# untitled.net
KiCad netlist of a schematic drawn in EAGLE
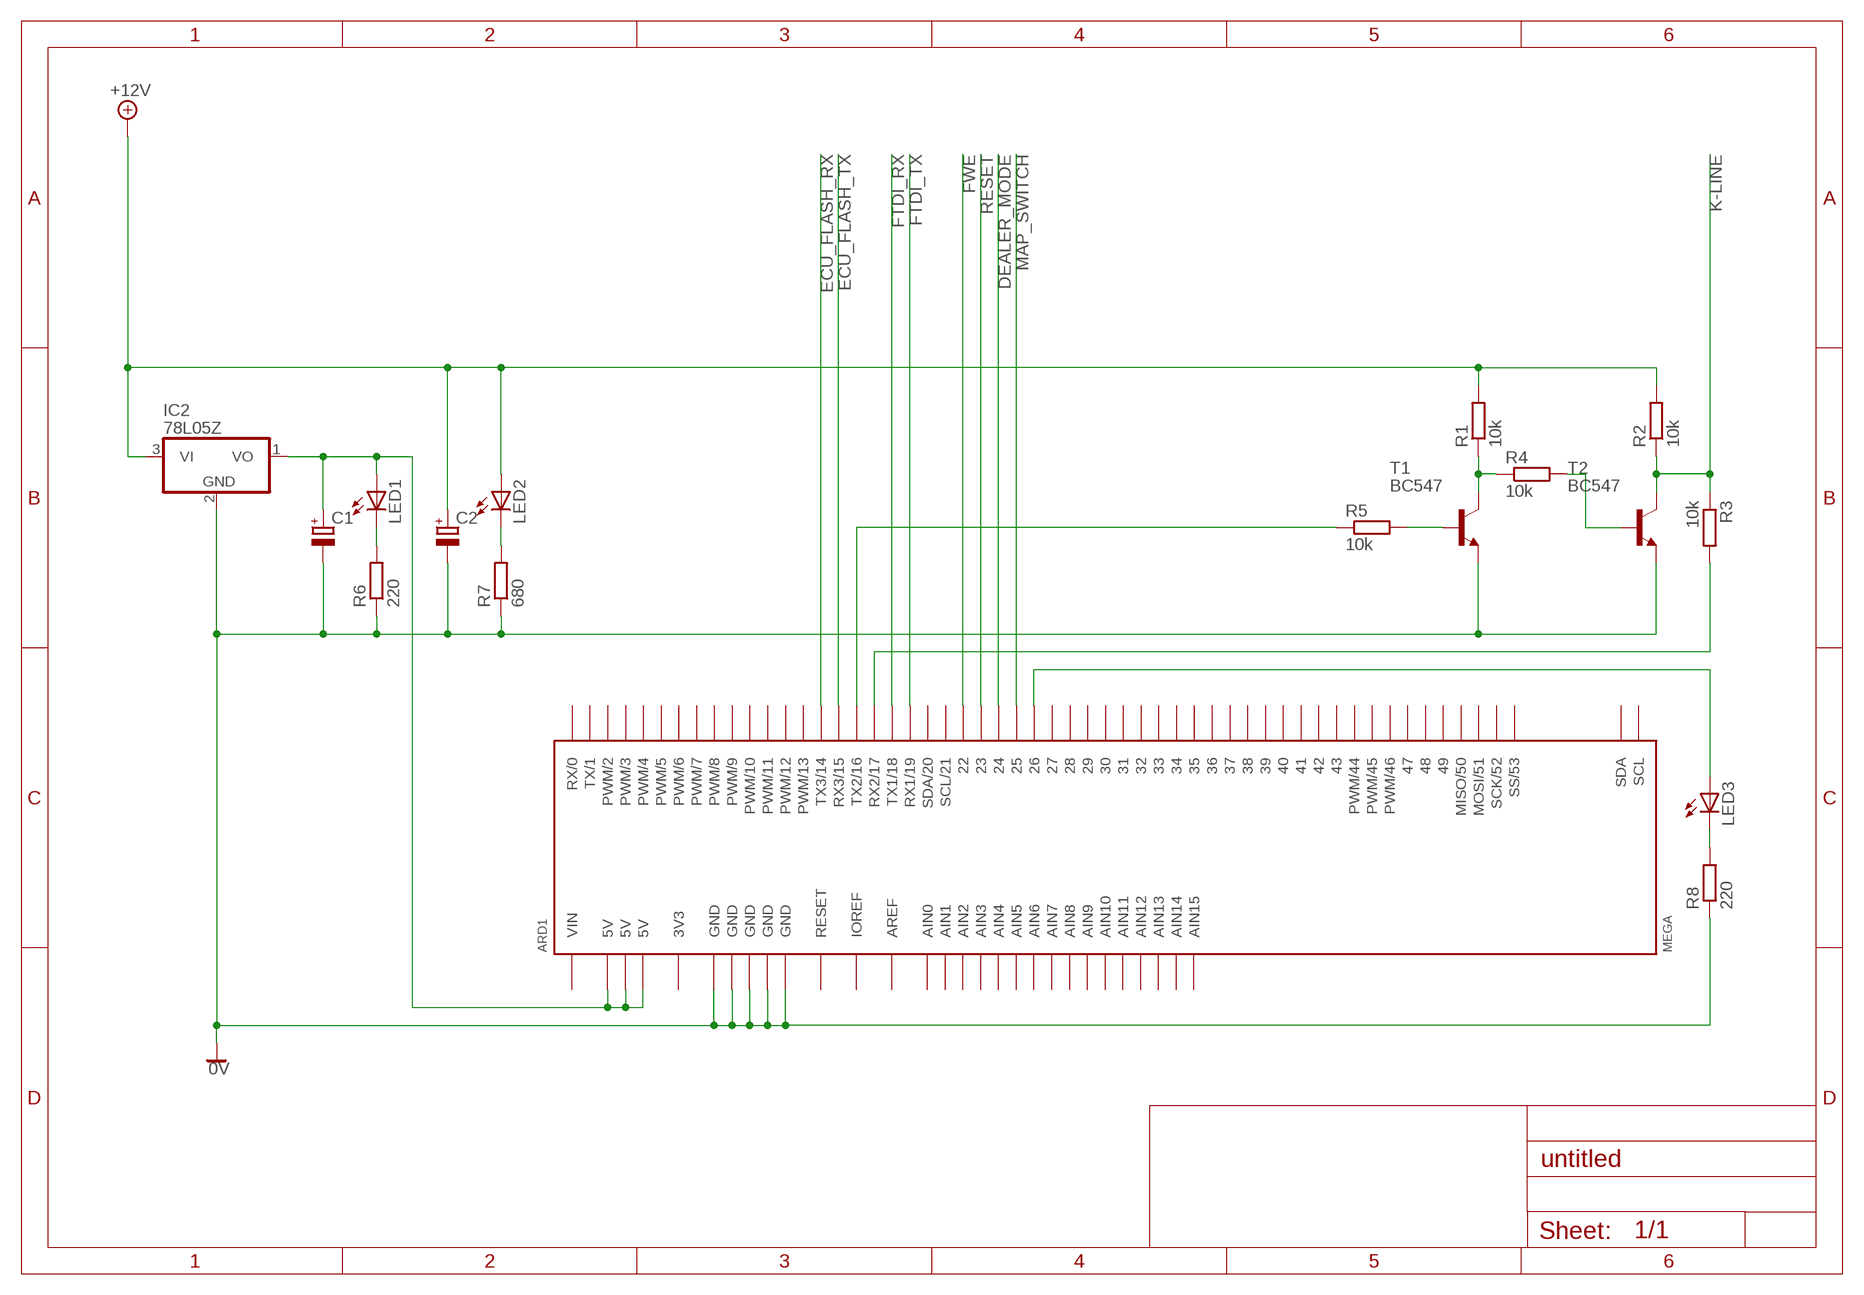
[diagram p0: schematic, sheet 1]

(export (version "E")
  (design (tool "Eeschema 10.0.6"))
  (components
    (comp (ref "ARD1")
      (value "MEGA")
      (footprint "eagle-import:MEGA")
      (libsource (lib "eagle-import") (part "MEGA"))
    )
    (comp (ref "C1")
      (value "CPOL-EUE1.8-4")
      (footprint "eagle-import:E1,8-4")
      (libsource (lib "eagle-import") (part "CPOL-EUE1.8-4"))
    )
    (comp (ref "C2")
      (value "CPOL-EUE1.8-4")
      (footprint "eagle-import:E1,8-4")
      (libsource (lib "eagle-import") (part "CPOL-EUE1.8-4"))
    )
    (comp (ref "IC2")
      (value "78L05Z")
      (footprint "eagle-import:TO92")
      (libsource (lib "eagle-import") (part "78ZL05"))
    )
    (comp (ref "LED1")
      (value "LED")
      (footprint "eagle-import:SMARTLED-TTW")
      (libsource (lib "eagle-import") (part "LED"))
    )
    (comp (ref "LED2")
      (value "LED")
      (footprint "eagle-import:SMARTLED-TTW")
      (libsource (lib "eagle-import") (part "LED"))
    )
    (comp (ref "LED3")
      (value "LED")
      (footprint "eagle-import:SMARTLED-TTW")
      (libsource (lib "eagle-import") (part "LED"))
    )
    (comp (ref "R1")
      (value "10k")
      (footprint "eagle-import:0204_5")
      (libsource (lib "eagle-import") (part "R-EU_0204/5"))
    )
    (comp (ref "R2")
      (value "10k")
      (footprint "eagle-import:0204_5")
      (libsource (lib "eagle-import") (part "R-EU_0204/5"))
    )
    (comp (ref "R3")
      (value "10k")
      (footprint "eagle-import:0204_5")
      (libsource (lib "eagle-import") (part "R-EU_0204/5"))
    )
    (comp (ref "R4")
      (value "10k")
      (footprint "eagle-import:0204_5")
      (libsource (lib "eagle-import") (part "R-EU_0204/5"))
    )
    (comp (ref "R5")
      (value "10k")
      (footprint "eagle-import:0204_5")
      (libsource (lib "eagle-import") (part "R-EU_0204/5"))
    )
    (comp (ref "R6")
      (value "220")
      (footprint "eagle-import:0204_5")
      (libsource (lib "eagle-import") (part "R-EU_0204/5"))
    )
    (comp (ref "R7")
      (value "680")
      (footprint "eagle-import:0204_5")
      (libsource (lib "eagle-import") (part "R-EU_0204/5"))
    )
    (comp (ref "R8")
      (value "220")
      (footprint "eagle-import:0204_5")
      (libsource (lib "eagle-import") (part "R-EU_0204/5"))
    )
    (comp (ref "T1")
      (value "BC547")
      (footprint "eagle-import:TO92")
      (libsource (lib "eagle-import") (part "BC547"))
    )
    (comp (ref "T2")
      (value "BC547")
      (footprint "eagle-import:TO92")
      (libsource (lib "eagle-import") (part "BC547"))
    )
  )
  (nets
    (net (code "1") (name "+12V") (class "Default")
      (node (ref "C2") (pin "+") (pinfunction "+_+") (pintype "passive"))
      (node (ref "IC2") (pin "3") (pinfunction "VI_3") (pintype "input"))
      (node (ref "LED2") (pin "A@1") (pinfunction "A_A@1") (pintype "passive"))
      (node (ref "R1") (pin "2") (pinfunction "2_2") (pintype "passive"))
      (node (ref "R2") (pin "2") (pinfunction "2_2") (pintype "passive"))
    )
    (net (code "2") (name "/3V3") (class "Default")
      (node (ref "ARD1") (pin "3V3") (pinfunction "3V3_3V3") (pintype "power_in"))
    )
    (net (code "3") (name "/AREF") (class "Default")
      (node (ref "ARD1") (pin "AREF") (pinfunction "AREF_AREF") (pintype "power_in"))
    )
    (net (code "4") (name "/DEALER_MODE") (class "Default")
      (node (ref "ARD1") (pin "24") (pinfunction "24_24") (pintype "bidirectional"))
    )
    (net (code "5") (name "/ECU_FLASH_RX") (class "Default")
      (node (ref "ARD1") (pin "14") (pinfunction "TX3/14_14") (pintype "bidirectional"))
    )
    (net (code "6") (name "/ECU_FLASH_TX") (class "Default")
      (node (ref "ARD1") (pin "15") (pinfunction "RX3/15_15") (pintype "bidirectional"))
    )
    (net (code "7") (name "/FTDI_RX") (class "Default")
      (node (ref "ARD1") (pin "18") (pinfunction "TX1/18_18") (pintype "bidirectional"))
    )
    (net (code "8") (name "/FTDI_TX") (class "Default")
      (node (ref "ARD1") (pin "19") (pinfunction "RX1/19_19") (pintype "bidirectional"))
    )
    (net (code "9") (name "/FWE") (class "Default")
      (node (ref "ARD1") (pin "22") (pinfunction "22_22") (pintype "bidirectional"))
    )
    (net (code "10") (name "/IOREF") (class "Default")
      (node (ref "ARD1") (pin "IOREF") (pinfunction "IOREF_IOREF") (pintype "power_in"))
    )
    (net (code "11") (name "/K-LINE") (class "Default")
      (node (ref "R2") (pin "1") (pinfunction "1_1") (pintype "passive"))
      (node (ref "R3") (pin "1") (pinfunction "1_1") (pintype "passive"))
      (node (ref "T2") (pin "3") (pinfunction "C_3") (pintype "passive"))
    )
    (net (code "12") (name "/MAP_SWITCH") (class "Default")
      (node (ref "ARD1") (pin "25") (pinfunction "25_25") (pintype "bidirectional"))
    )
    (net (code "13") (name "/RESET") (class "Default")
      (node (ref "ARD1") (pin "23") (pinfunction "23_23") (pintype "bidirectional"))
    )
    (net (code "14") (name "/VIN") (class "Default")
      (node (ref "ARD1") (pin "VIN") (pinfunction "VIN_VIN") (pintype "power_in"))
    )
    (net (code "15") (name "0V") (class "Default")
      (node (ref "ARD1") (pin "GND1") (pinfunction "GND_GND1") (pintype "power_in"))
      (node (ref "ARD1") (pin "GND2") (pinfunction "GND_GND2") (pintype "power_in"))
      (node (ref "ARD1") (pin "GND3") (pinfunction "GND_GND3") (pintype "power_in"))
      (node (ref "ARD1") (pin "GND4") (pinfunction "GND_GND4") (pintype "power_in"))
      (node (ref "ARD1") (pin "GND5") (pinfunction "GND_GND5") (pintype "power_in"))
      (node (ref "C1") (pin "-") (pinfunction "-_-") (pintype "passive"))
      (node (ref "C2") (pin "-") (pinfunction "-_-") (pintype "passive"))
      (node (ref "IC2") (pin "2") (pinfunction "GND_2") (pintype "passive"))
      (node (ref "R6") (pin "1") (pinfunction "1_1") (pintype "passive"))
      (node (ref "R7") (pin "1") (pinfunction "1_1") (pintype "passive"))
      (node (ref "R8") (pin "1") (pinfunction "1_1") (pintype "passive"))
      (node (ref "T1") (pin "1") (pinfunction "E_1") (pintype "passive"))
      (node (ref "T2") (pin "1") (pinfunction "E_1") (pintype "passive"))
    )
    (net (code "16") (name "Net-(ARD1-RX2{slash}17)") (class "Default")
      (node (ref "ARD1") (pin "17") (pinfunction "RX2/17_17") (pintype "bidirectional"))
      (node (ref "R3") (pin "2") (pinfunction "2_2") (pintype "passive"))
    )
    (net (code "17") (name "Net-(ARD1-TX2{slash}16)") (class "Default")
      (node (ref "ARD1") (pin "16") (pinfunction "TX2/16_16") (pintype "bidirectional"))
      (node (ref "R5") (pin "1") (pinfunction "1_1") (pintype "passive"))
    )
    (net (code "18") (name "Net-(IC2-VO)") (class "Default")
      (node (ref "ARD1") (pin "5V1") (pinfunction "5V_5V1") (pintype "power_in"))
      (node (ref "ARD1") (pin "5V2") (pinfunction "5V_5V2") (pintype "power_in"))
      (node (ref "ARD1") (pin "5V3") (pinfunction "5V_5V3") (pintype "power_in"))
      (node (ref "C1") (pin "+") (pinfunction "+_+") (pintype "passive"))
      (node (ref "IC2") (pin "1") (pinfunction "VO_1") (pintype "passive"))
      (node (ref "LED1") (pin "A@1") (pinfunction "A_A@1") (pintype "passive"))
    )
    (net (code "19") (name "Net-(LED1-C)") (class "Default")
      (node (ref "LED1") (pin "C@1") (pinfunction "C_C@1") (pintype "passive"))
      (node (ref "R6") (pin "2") (pinfunction "2_2") (pintype "passive"))
    )
    (net (code "20") (name "Net-(LED2-C)") (class "Default")
      (node (ref "LED2") (pin "C@1") (pinfunction "C_C@1") (pintype "passive"))
      (node (ref "R7") (pin "2") (pinfunction "2_2") (pintype "passive"))
    )
    (net (code "21") (name "Net-(LED3-A)") (class "Default")
      (node (ref "ARD1") (pin "26") (pinfunction "26_26") (pintype "bidirectional"))
      (node (ref "LED3") (pin "A@1") (pinfunction "A_A@1") (pintype "passive"))
    )
    (net (code "22") (name "Net-(LED3-C)") (class "Default")
      (node (ref "LED3") (pin "C@1") (pinfunction "C_C@1") (pintype "passive"))
      (node (ref "R8") (pin "2") (pinfunction "2_2") (pintype "passive"))
    )
    (net (code "23") (name "Net-(T1-B)") (class "Default")
      (node (ref "R5") (pin "2") (pinfunction "2_2") (pintype "passive"))
      (node (ref "T1") (pin "2") (pinfunction "B_2") (pintype "passive"))
    )
    (net (code "24") (name "Net-(T1-C)") (class "Default")
      (node (ref "R1") (pin "1") (pinfunction "1_1") (pintype "passive"))
      (node (ref "R4") (pin "1") (pinfunction "1_1") (pintype "passive"))
      (node (ref "T1") (pin "3") (pinfunction "C_3") (pintype "passive"))
    )
    (net (code "25") (name "Net-(T2-B)") (class "Default")
      (node (ref "R4") (pin "2") (pinfunction "2_2") (pintype "passive"))
      (node (ref "T2") (pin "2") (pinfunction "B_2") (pintype "passive"))
    )
    (net (code "26") (name "unconnected-(ARD1-MISO{slash}50-Pad50)") (class "Default")
      (node (ref "ARD1") (pin "50") (pinfunction "MISO/50_50") (pintype "bidirectional"))
    )
    (net (code "27") (name "unconnected-(ARD1-MOSI{slash}51-Pad51)") (class "Default")
      (node (ref "ARD1") (pin "51") (pinfunction "MOSI/51_51") (pintype "bidirectional"))
    )
    (net (code "28") (name "unconnected-(ARD1-PWM{slash}2-Pad2)") (class "Default")
      (node (ref "ARD1") (pin "2") (pinfunction "PWM/2_2") (pintype "bidirectional"))
    )
    (net (code "29") (name "unconnected-(ARD1-PWM{slash}3-Pad3)") (class "Default")
      (node (ref "ARD1") (pin "3") (pinfunction "PWM/3_3") (pintype "bidirectional"))
    )
    (net (code "30") (name "unconnected-(ARD1-PWM{slash}4-Pad4)") (class "Default")
      (node (ref "ARD1") (pin "4") (pinfunction "PWM/4_4") (pintype "bidirectional"))
    )
    (net (code "31") (name "unconnected-(ARD1-PWM{slash}5-Pad5)") (class "Default")
      (node (ref "ARD1") (pin "5") (pinfunction "PWM/5_5") (pintype "bidirectional"))
    )
    (net (code "32") (name "unconnected-(ARD1-PWM{slash}6-Pad6)") (class "Default")
      (node (ref "ARD1") (pin "6") (pinfunction "PWM/6_6") (pintype "bidirectional"))
    )
    (net (code "33") (name "unconnected-(ARD1-PWM{slash}7-Pad7)") (class "Default")
      (node (ref "ARD1") (pin "7") (pinfunction "PWM/7_7") (pintype "bidirectional"))
    )
    (net (code "34") (name "unconnected-(ARD1-PWM{slash}8-Pad8)") (class "Default")
      (node (ref "ARD1") (pin "8") (pinfunction "PWM/8_8") (pintype "bidirectional"))
    )
    (net (code "35") (name "unconnected-(ARD1-PWM{slash}9-Pad9)") (class "Default")
      (node (ref "ARD1") (pin "9") (pinfunction "PWM/9_9") (pintype "bidirectional"))
    )
    (net (code "36") (name "unconnected-(ARD1-PWM{slash}10-Pad10)") (class "Default")
      (node (ref "ARD1") (pin "10") (pinfunction "PWM/10_10") (pintype "bidirectional"))
    )
    (net (code "37") (name "unconnected-(ARD1-PWM{slash}11-Pad11)") (class "Default")
      (node (ref "ARD1") (pin "11") (pinfunction "PWM/11_11") (pintype "bidirectional"))
    )
    (net (code "38") (name "unconnected-(ARD1-PWM{slash}12-Pad12)") (class "Default")
      (node (ref "ARD1") (pin "12") (pinfunction "PWM/12_12") (pintype "bidirectional"))
    )
    (net (code "39") (name "unconnected-(ARD1-PWM{slash}13-Pad13)") (class "Default")
      (node (ref "ARD1") (pin "13") (pinfunction "PWM/13_13") (pintype "bidirectional"))
    )
    (net (code "40") (name "unconnected-(ARD1-PWM{slash}44-Pad44)") (class "Default")
      (node (ref "ARD1") (pin "44") (pinfunction "PWM/44_44") (pintype "bidirectional"))
    )
    (net (code "41") (name "unconnected-(ARD1-PWM{slash}45-Pad45)") (class "Default")
      (node (ref "ARD1") (pin "45") (pinfunction "PWM/45_45") (pintype "bidirectional"))
    )
    (net (code "42") (name "unconnected-(ARD1-PWM{slash}46-Pad46)") (class "Default")
      (node (ref "ARD1") (pin "46") (pinfunction "PWM/46_46") (pintype "bidirectional"))
    )
    (net (code "43") (name "unconnected-(ARD1-Pad27)") (class "Default")
      (node (ref "ARD1") (pin "27") (pinfunction "27_27") (pintype "bidirectional"))
    )
    (net (code "44") (name "unconnected-(ARD1-Pad28)") (class "Default")
      (node (ref "ARD1") (pin "28") (pinfunction "28_28") (pintype "bidirectional"))
    )
    (net (code "45") (name "unconnected-(ARD1-Pad29)") (class "Default")
      (node (ref "ARD1") (pin "29") (pinfunction "29_29") (pintype "bidirectional"))
    )
    (net (code "46") (name "unconnected-(ARD1-Pad30)") (class "Default")
      (node (ref "ARD1") (pin "30") (pinfunction "30_30") (pintype "bidirectional"))
    )
    (net (code "47") (name "unconnected-(ARD1-Pad31)") (class "Default")
      (node (ref "ARD1") (pin "31") (pinfunction "31_31") (pintype "bidirectional"))
    )
    (net (code "48") (name "unconnected-(ARD1-Pad32)") (class "Default")
      (node (ref "ARD1") (pin "32") (pinfunction "32_32") (pintype "bidirectional"))
    )
    (net (code "49") (name "unconnected-(ARD1-Pad33)") (class "Default")
      (node (ref "ARD1") (pin "33") (pinfunction "33_33") (pintype "bidirectional"))
    )
    (net (code "50") (name "unconnected-(ARD1-Pad34)") (class "Default")
      (node (ref "ARD1") (pin "34") (pinfunction "34_34") (pintype "bidirectional"))
    )
    (net (code "51") (name "unconnected-(ARD1-Pad35)") (class "Default")
      (node (ref "ARD1") (pin "35") (pinfunction "35_35") (pintype "bidirectional"))
    )
    (net (code "52") (name "unconnected-(ARD1-Pad36)") (class "Default")
      (node (ref "ARD1") (pin "36") (pinfunction "36_36") (pintype "bidirectional"))
    )
    (net (code "53") (name "unconnected-(ARD1-Pad37)") (class "Default")
      (node (ref "ARD1") (pin "37") (pinfunction "37_37") (pintype "bidirectional"))
    )
    (net (code "54") (name "unconnected-(ARD1-Pad38)") (class "Default")
      (node (ref "ARD1") (pin "38") (pinfunction "38_38") (pintype "bidirectional"))
    )
    (net (code "55") (name "unconnected-(ARD1-Pad39)") (class "Default")
      (node (ref "ARD1") (pin "39") (pinfunction "39_39") (pintype "bidirectional"))
    )
    (net (code "56") (name "unconnected-(ARD1-Pad40)") (class "Default")
      (node (ref "ARD1") (pin "40") (pinfunction "40_40") (pintype "bidirectional"))
    )
    (net (code "57") (name "unconnected-(ARD1-Pad41)") (class "Default")
      (node (ref "ARD1") (pin "41") (pinfunction "41_41") (pintype "bidirectional"))
    )
    (net (code "58") (name "unconnected-(ARD1-Pad42)") (class "Default")
      (node (ref "ARD1") (pin "42") (pinfunction "42_42") (pintype "bidirectional"))
    )
    (net (code "59") (name "unconnected-(ARD1-Pad43)") (class "Default")
      (node (ref "ARD1") (pin "43") (pinfunction "43_43") (pintype "bidirectional"))
    )
    (net (code "60") (name "unconnected-(ARD1-Pad47)") (class "Default")
      (node (ref "ARD1") (pin "47") (pinfunction "47_47") (pintype "bidirectional"))
    )
    (net (code "61") (name "unconnected-(ARD1-Pad48)") (class "Default")
      (node (ref "ARD1") (pin "48") (pinfunction "48_48") (pintype "bidirectional"))
    )
    (net (code "62") (name "unconnected-(ARD1-Pad49)") (class "Default")
      (node (ref "ARD1") (pin "49") (pinfunction "49_49") (pintype "bidirectional"))
    )
    (net (code "63") (name "unconnected-(ARD1-PadAIN0)") (class "Default")
      (node (ref "ARD1") (pin "AIN0") (pinfunction "AIN0_AIN0") (pintype "bidirectional"))
    )
    (net (code "64") (name "unconnected-(ARD1-PadAIN1)") (class "Default")
      (node (ref "ARD1") (pin "AIN1") (pinfunction "AIN1_AIN1") (pintype "bidirectional"))
    )
    (net (code "65") (name "unconnected-(ARD1-PadAIN2)") (class "Default")
      (node (ref "ARD1") (pin "AIN2") (pinfunction "AIN2_AIN2") (pintype "bidirectional"))
    )
    (net (code "66") (name "unconnected-(ARD1-PadAIN3)") (class "Default")
      (node (ref "ARD1") (pin "AIN3") (pinfunction "AIN3_AIN3") (pintype "bidirectional"))
    )
    (net (code "67") (name "unconnected-(ARD1-PadAIN4)") (class "Default")
      (node (ref "ARD1") (pin "AIN4") (pinfunction "AIN4_AIN4") (pintype "bidirectional"))
    )
    (net (code "68") (name "unconnected-(ARD1-PadAIN5)") (class "Default")
      (node (ref "ARD1") (pin "AIN5") (pinfunction "AIN5_AIN5") (pintype "bidirectional"))
    )
    (net (code "69") (name "unconnected-(ARD1-PadAIN6)") (class "Default")
      (node (ref "ARD1") (pin "AIN6") (pinfunction "AIN6_AIN6") (pintype "bidirectional"))
    )
    (net (code "70") (name "unconnected-(ARD1-PadAIN7)") (class "Default")
      (node (ref "ARD1") (pin "AIN7") (pinfunction "AIN7_AIN7") (pintype "bidirectional"))
    )
    (net (code "71") (name "unconnected-(ARD1-PadAIN8)") (class "Default")
      (node (ref "ARD1") (pin "AIN8") (pinfunction "AIN8_AIN8") (pintype "bidirectional"))
    )
    (net (code "72") (name "unconnected-(ARD1-PadAIN9)") (class "Default")
      (node (ref "ARD1") (pin "AIN9") (pinfunction "AIN9_AIN9") (pintype "bidirectional"))
    )
    (net (code "73") (name "unconnected-(ARD1-PadAIN10)") (class "Default")
      (node (ref "ARD1") (pin "AIN10") (pinfunction "AIN10_AIN10") (pintype "bidirectional"))
    )
    (net (code "74") (name "unconnected-(ARD1-PadAIN11)") (class "Default")
      (node (ref "ARD1") (pin "AIN11") (pinfunction "AIN11_AIN11") (pintype "bidirectional"))
    )
    (net (code "75") (name "unconnected-(ARD1-PadAIN12)") (class "Default")
      (node (ref "ARD1") (pin "AIN12") (pinfunction "AIN12_AIN12") (pintype "bidirectional"))
    )
    (net (code "76") (name "unconnected-(ARD1-PadAIN13)") (class "Default")
      (node (ref "ARD1") (pin "AIN13") (pinfunction "AIN13_AIN13") (pintype "bidirectional"))
    )
    (net (code "77") (name "unconnected-(ARD1-PadAIN14)") (class "Default")
      (node (ref "ARD1") (pin "AIN14") (pinfunction "AIN14_AIN14") (pintype "bidirectional"))
    )
    (net (code "78") (name "unconnected-(ARD1-PadAIN15)") (class "Default")
      (node (ref "ARD1") (pin "AIN15") (pinfunction "AIN15_AIN15") (pintype "bidirectional"))
    )
    (net (code "79") (name "unconnected-(ARD1-PadSCL)") (class "Default")
      (node (ref "ARD1") (pin "SCL") (pinfunction "SCL_SCL") (pintype "bidirectional"))
    )
    (net (code "80") (name "unconnected-(ARD1-PadSDA)") (class "Default")
      (node (ref "ARD1") (pin "SDA") (pinfunction "SDA_SDA") (pintype "bidirectional"))
    )
    (net (code "81") (name "unconnected-(ARD1-RESET-PadRST)") (class "Default")
      (node (ref "ARD1") (pin "RST") (pinfunction "RESET_RST") (pintype "bidirectional"))
    )
    (net (code "82") (name "unconnected-(ARD1-RX{slash}0-Pad0)") (class "Default")
      (node (ref "ARD1") (pin "0") (pinfunction "RX/0_0") (pintype "bidirectional"))
    )
    (net (code "83") (name "unconnected-(ARD1-SCK{slash}52-Pad52)") (class "Default")
      (node (ref "ARD1") (pin "52") (pinfunction "SCK/52_52") (pintype "bidirectional"))
    )
    (net (code "84") (name "unconnected-(ARD1-SCL{slash}21-Pad21)") (class "Default")
      (node (ref "ARD1") (pin "21") (pinfunction "SCL/21_21") (pintype "bidirectional"))
    )
    (net (code "85") (name "unconnected-(ARD1-SDA{slash}20-Pad20)") (class "Default")
      (node (ref "ARD1") (pin "20") (pinfunction "SDA/20_20") (pintype "bidirectional"))
    )
    (net (code "86") (name "unconnected-(ARD1-SS{slash}53-Pad53)") (class "Default")
      (node (ref "ARD1") (pin "53") (pinfunction "SS/53_53") (pintype "bidirectional"))
    )
    (net (code "87") (name "unconnected-(ARD1-TX{slash}1-Pad1)") (class "Default")
      (node (ref "ARD1") (pin "1") (pinfunction "TX/1_1") (pintype "bidirectional"))
    )
  )
)
